# ControlC.net
KiCad netlist of a schematic drawn in EAGLE
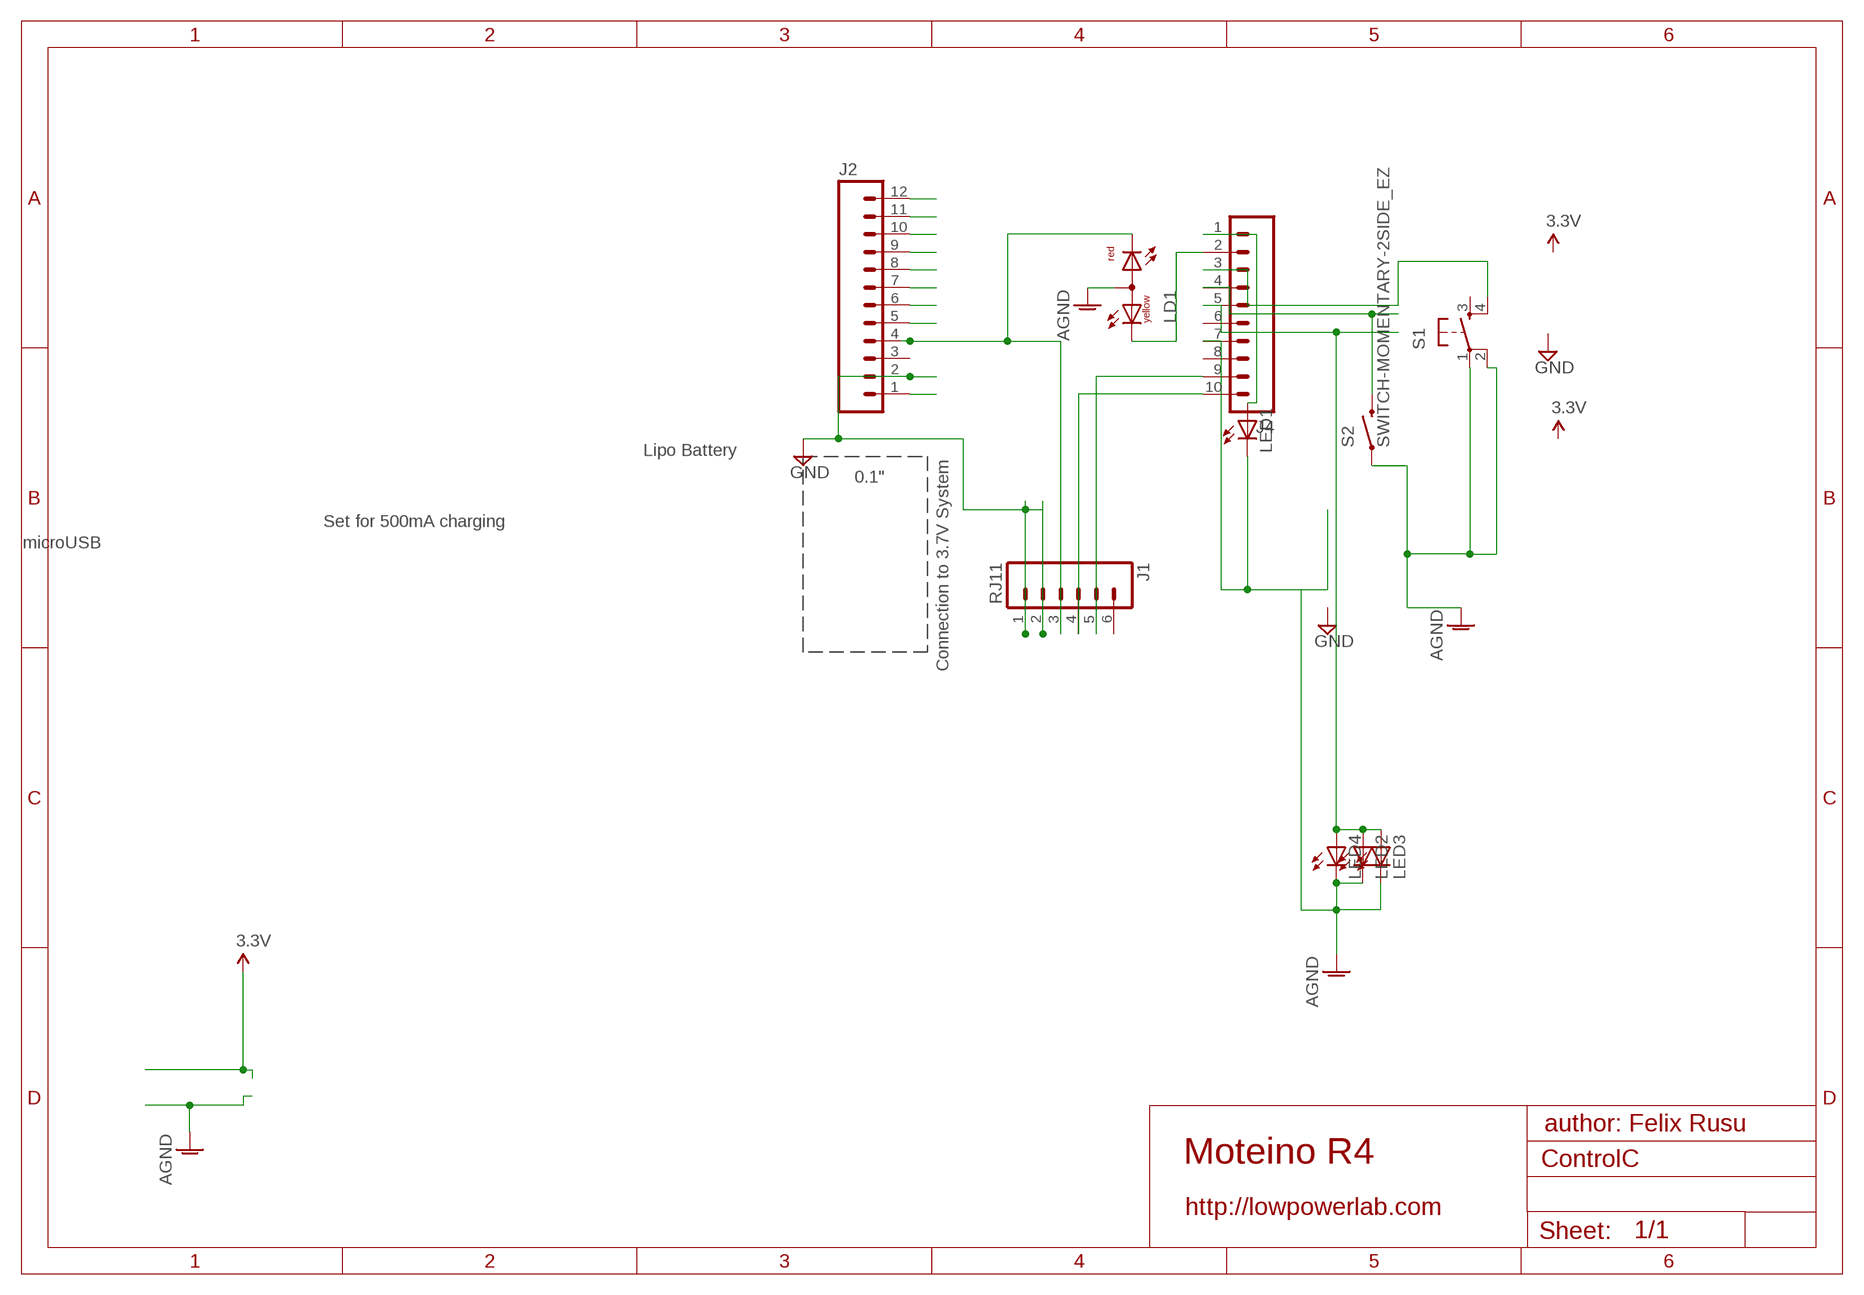
[diagram p0: schematic, sheet 1]

(export (version "E")
  (design (tool "Eeschema 10.0.6"))
  (components
    (comp (ref "J1")
      (value "RJ11")
      (footprint "eagle-import:RJ11-6")
      (libsource (lib "eagle-import") (part "RJ11-6PTH"))
    )
    (comp (ref "J2")
      (value "M12PTH")
      (footprint "eagle-import:1X12")
      (libsource (lib "eagle-import") (part "M12PTH"))
    )
    (comp (ref "J4")
      (value "M10SILK_FEMALE_PTH")
      (footprint "eagle-import:1X10")
      (libsource (lib "eagle-import") (part "M10SILK_FEMALE_PTH"))
    )
    (comp (ref "LD1")
      (value "DUOLED-RY-A")
      (footprint "eagle-import:DUOLED-A-5MM")
      (libsource (lib "eagle-import") (part "DUOLED-RY-A"))
    )
    (comp (ref "LED1")
      (value "LED3MM")
      (footprint "eagle-import:LED3MM")
      (libsource (lib "eagle-import") (part "LED3MM"))
    )
    (comp (ref "LED2")
      (value "LED3MM")
      (footprint "eagle-import:LED3MM")
      (libsource (lib "eagle-import") (part "LED3MM"))
    )
    (comp (ref "LED3")
      (value "LED3MM")
      (footprint "eagle-import:LED3MM")
      (libsource (lib "eagle-import") (part "LED3MM"))
    )
    (comp (ref "LED4")
      (value "LED3MM")
      (footprint "eagle-import:LED3MM")
      (libsource (lib "eagle-import") (part "LED3MM"))
    )
    (comp (ref "S1")
      (value "TAC_SWITCHPTH")
      (footprint "eagle-import:TACTILE-PTH")
      (libsource (lib "eagle-import") (part "TAC_SWITCHPTH"))
    )
    (comp (ref "S2")
      (value "SWITCH-MOMENTARY-2SIDE_EZ")
      (footprint "eagle-import:TACTILE-PTH-SIDEEZ")
      (libsource (lib "eagle-import") (part "SWITCH-MOMENTARY-2SIDE_EZ"))
    )
  )
  (nets
    (net (code "2") (name "AGND") (class "Default")
      (node (ref "J4") (pin "7") (pinfunction "7_7") (pintype "passive"))
      (node (ref "LD1") (pin "A") (pinfunction "A_A") (pintype "passive"))
      (node (ref "LED1") (pin "K") (pinfunction "C_K") (pintype "passive"))
      (node (ref "LED2") (pin "K") (pinfunction "C_K") (pintype "passive"))
      (node (ref "LED3") (pin "K") (pinfunction "C_K") (pintype "passive"))
      (node (ref "LED4") (pin "K") (pinfunction "C_K") (pintype "passive"))
      (node (ref "S1") (pin "1") (pinfunction "1_1") (pintype "passive"))
      (node (ref "S1") (pin "2") (pinfunction "2_2") (pintype "passive"))
      (node (ref "S2") (pin "1") (pinfunction "1_1") (pintype "passive"))
    )
    (net (code "3") (name "GND") (class "Default")
      (node (ref "J1") (pin "1") (pinfunction "1_1") (pintype "passive"))
      (node (ref "J1") (pin "2") (pinfunction "2_2") (pintype "passive"))
      (node (ref "J2") (pin "2") (pinfunction "2_2") (pintype "passive"))
    )
    (net (code "4") (name "Net-(J1-Pad3)") (class "Default")
      (node (ref "J1") (pin "3") (pinfunction "3_3") (pintype "passive"))
      (node (ref "J2") (pin "4") (pinfunction "4_4") (pintype "passive"))
      (node (ref "LD1") (pin "CR") (pinfunction "CR_CR") (pintype "passive"))
    )
    (net (code "5") (name "Net-(J1-Pad4)") (class "Default")
      (node (ref "J1") (pin "4") (pinfunction "4_4") (pintype "passive"))
      (node (ref "J4") (pin "10") (pinfunction "10_10") (pintype "passive"))
    )
    (net (code "6") (name "Net-(J1-Pad5)") (class "Default")
      (node (ref "J1") (pin "5") (pinfunction "5_5") (pintype "passive"))
      (node (ref "J4") (pin "9") (pinfunction "9_9") (pintype "passive"))
    )
    (net (code "7") (name "Net-(J4-Pad1)") (class "Default")
      (node (ref "J4") (pin "1") (pinfunction "1_1") (pintype "passive"))
      (node (ref "LED1") (pin "A") (pinfunction "A_A") (pintype "passive"))
    )
    (net (code "8") (name "Net-(J4-Pad3)") (class "Default")
      (node (ref "J4") (pin "3") (pinfunction "3_3") (pintype "passive"))
      (node (ref "S1") (pin "4") (pinfunction "4_4") (pintype "passive"))
    )
    (net (code "9") (name "Net-(J4-Pad4)") (class "Default")
      (node (ref "J4") (pin "4") (pinfunction "4_4") (pintype "passive"))
      (node (ref "S2") (pin "2") (pinfunction "2_2") (pintype "passive"))
    )
    (net (code "10") (name "Net-(J4-Pad5)") (class "Default")
      (node (ref "J4") (pin "5") (pinfunction "5_5") (pintype "passive"))
      (node (ref "LED2") (pin "A") (pinfunction "A_A") (pintype "passive"))
      (node (ref "LED3") (pin "A") (pinfunction "A_A") (pintype "passive"))
      (node (ref "LED4") (pin "A") (pinfunction "A_A") (pintype "passive"))
    )
    (net (code "11") (name "Net-(LD1-CY)") (class "Default")
      (node (ref "J4") (pin "2") (pinfunction "2_2") (pintype "passive"))
      (node (ref "LD1") (pin "CX") (pinfunction "CY_CX") (pintype "passive"))
    )
    (net (code "12") (name "unconnected-(J1-Pad6)") (class "Default")
      (node (ref "J1") (pin "6") (pinfunction "6_6") (pintype "passive"))
    )
    (net (code "13") (name "unconnected-(J2-Pad1)") (class "Default")
      (node (ref "J2") (pin "1") (pinfunction "1_1") (pintype "passive"))
    )
    (net (code "14") (name "unconnected-(J2-Pad3)") (class "Default")
      (node (ref "J2") (pin "3") (pinfunction "3_3") (pintype "passive"))
    )
    (net (code "15") (name "unconnected-(J2-Pad5)") (class "Default")
      (node (ref "J2") (pin "5") (pinfunction "5_5") (pintype "passive"))
    )
    (net (code "16") (name "unconnected-(J2-Pad6)") (class "Default")
      (node (ref "J2") (pin "6") (pinfunction "6_6") (pintype "passive"))
    )
    (net (code "17") (name "unconnected-(J2-Pad7)") (class "Default")
      (node (ref "J2") (pin "7") (pinfunction "7_7") (pintype "passive"))
    )
    (net (code "18") (name "unconnected-(J2-Pad8)") (class "Default")
      (node (ref "J2") (pin "8") (pinfunction "8_8") (pintype "passive"))
    )
    (net (code "19") (name "unconnected-(J2-Pad9)") (class "Default")
      (node (ref "J2") (pin "9") (pinfunction "9_9") (pintype "passive"))
    )
    (net (code "20") (name "unconnected-(J2-Pad10)") (class "Default")
      (node (ref "J2") (pin "10") (pinfunction "10_10") (pintype "passive"))
    )
    (net (code "21") (name "unconnected-(J2-Pad11)") (class "Default")
      (node (ref "J2") (pin "11") (pinfunction "11_11") (pintype "passive"))
    )
    (net (code "22") (name "unconnected-(J2-Pad12)") (class "Default")
      (node (ref "J2") (pin "12") (pinfunction "12_12") (pintype "passive"))
    )
    (net (code "23") (name "unconnected-(J4-Pad6)") (class "Default")
      (node (ref "J4") (pin "6") (pinfunction "6_6") (pintype "passive"))
    )
    (net (code "24") (name "unconnected-(J4-Pad8)") (class "Default")
      (node (ref "J4") (pin "8") (pinfunction "8_8") (pintype "passive"))
    )
    (net (code "25") (name "unconnected-(S1-Pad3)") (class "Default")
      (node (ref "S1") (pin "3") (pinfunction "3_3") (pintype "passive"))
    )
  )
)
